# forcefoot.net
KiCad netlist of a schematic drawn in EAGLE
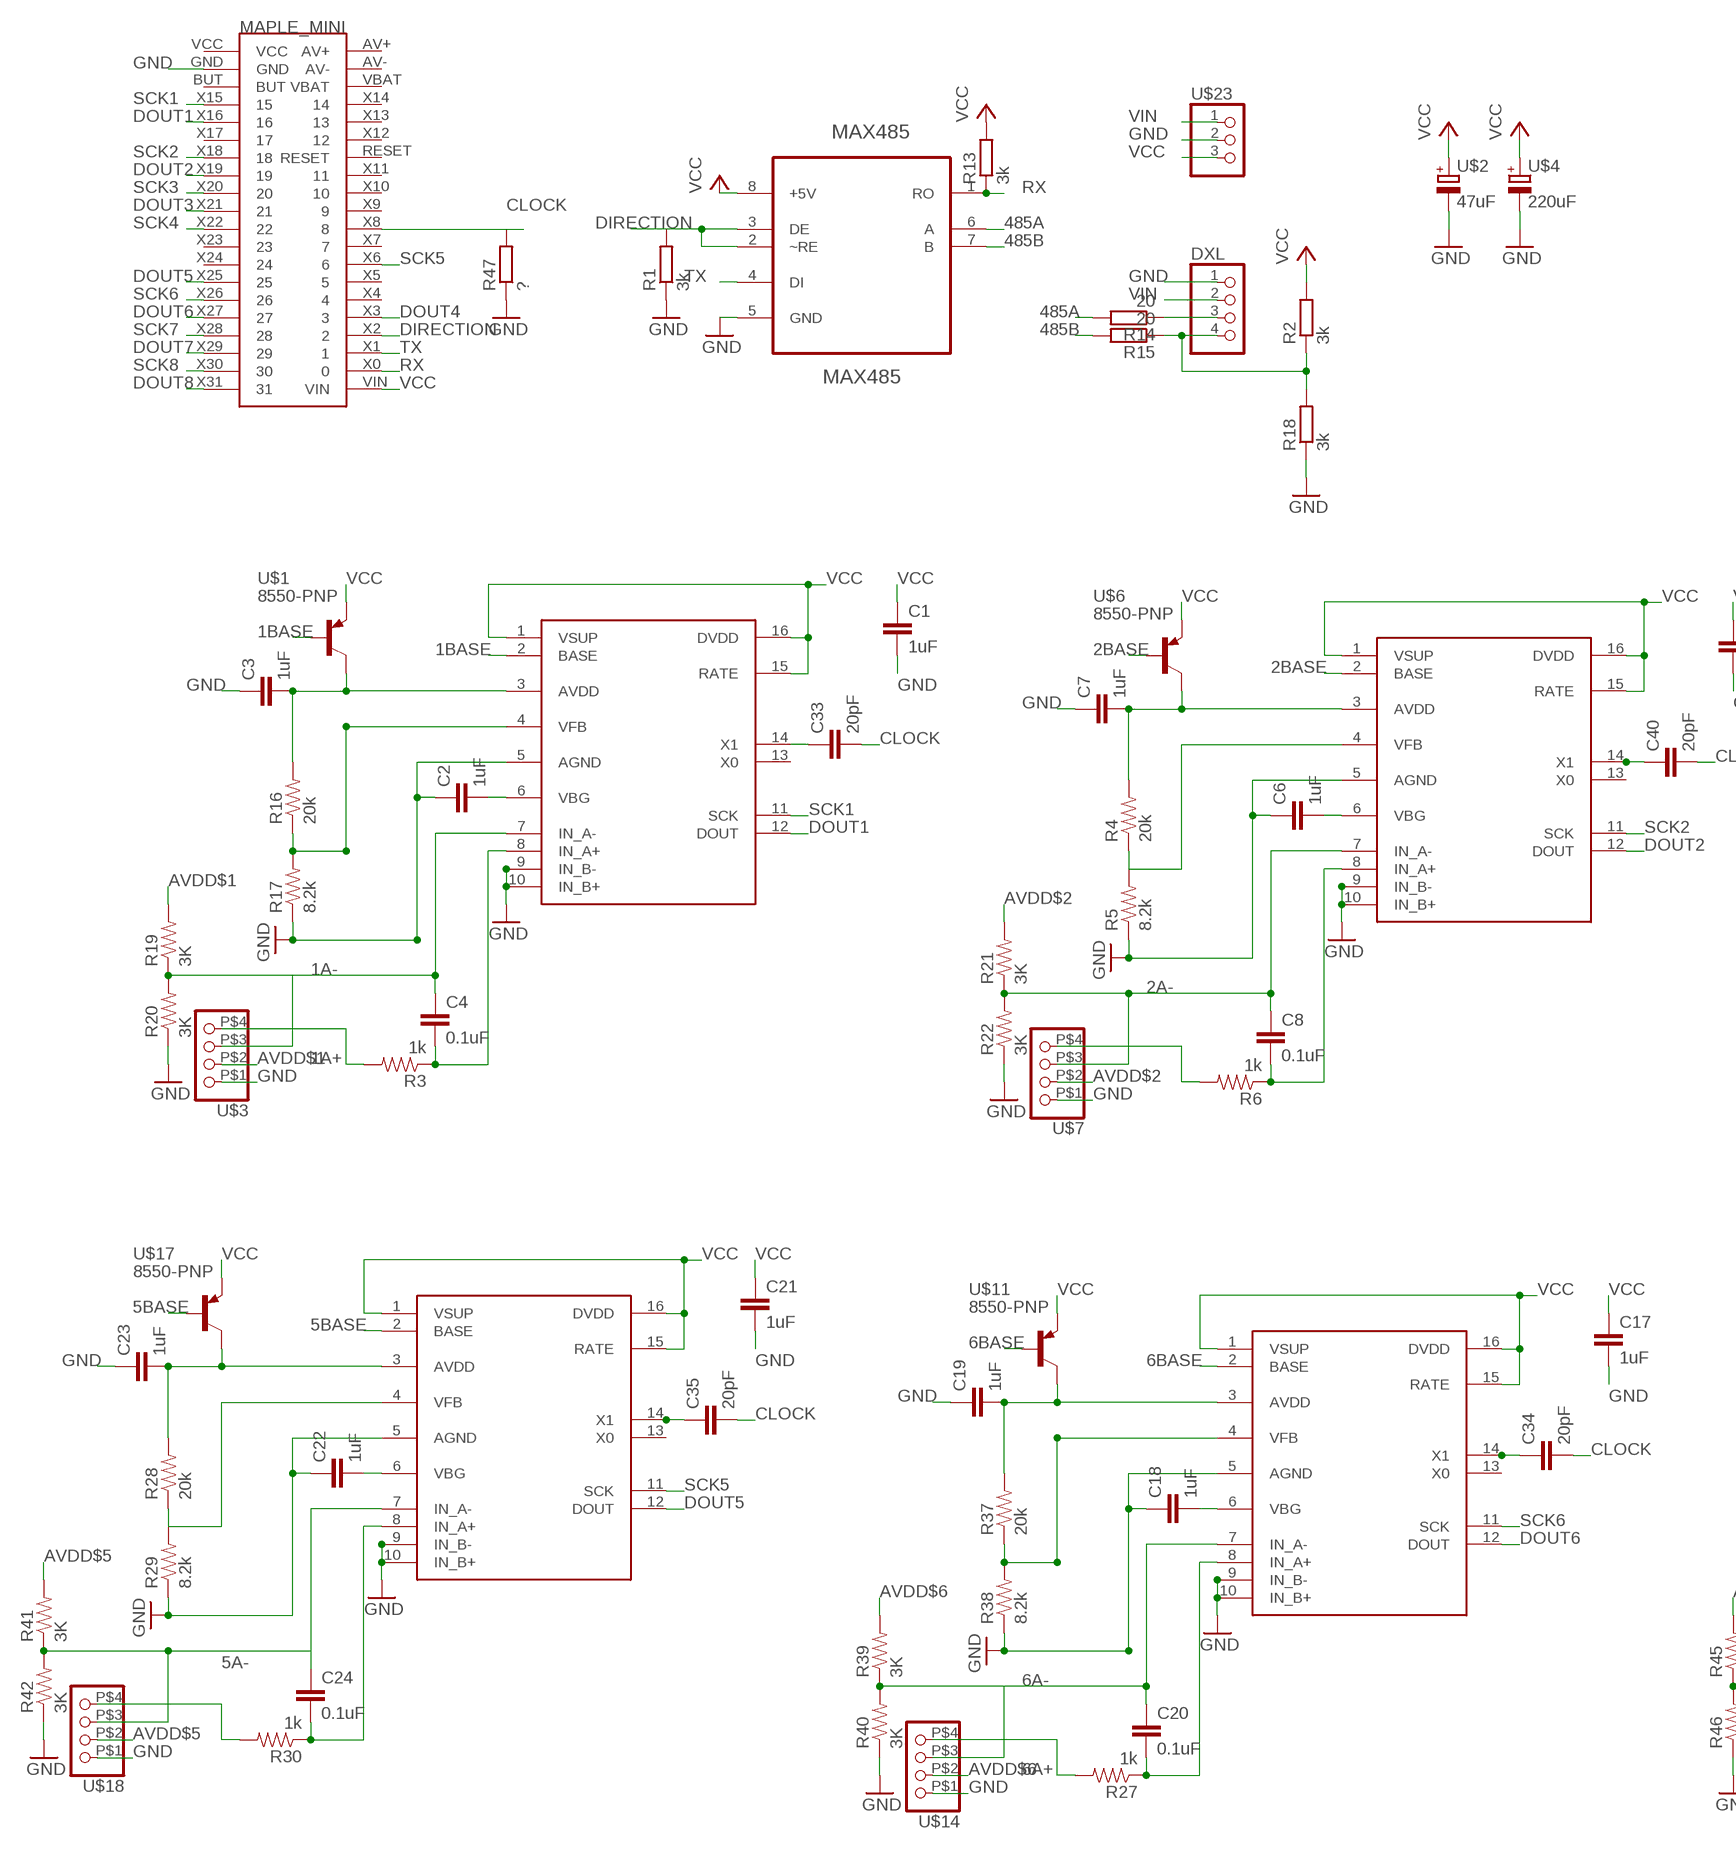
[diagram p0: schematic, sheet 1, part 1 of 2]
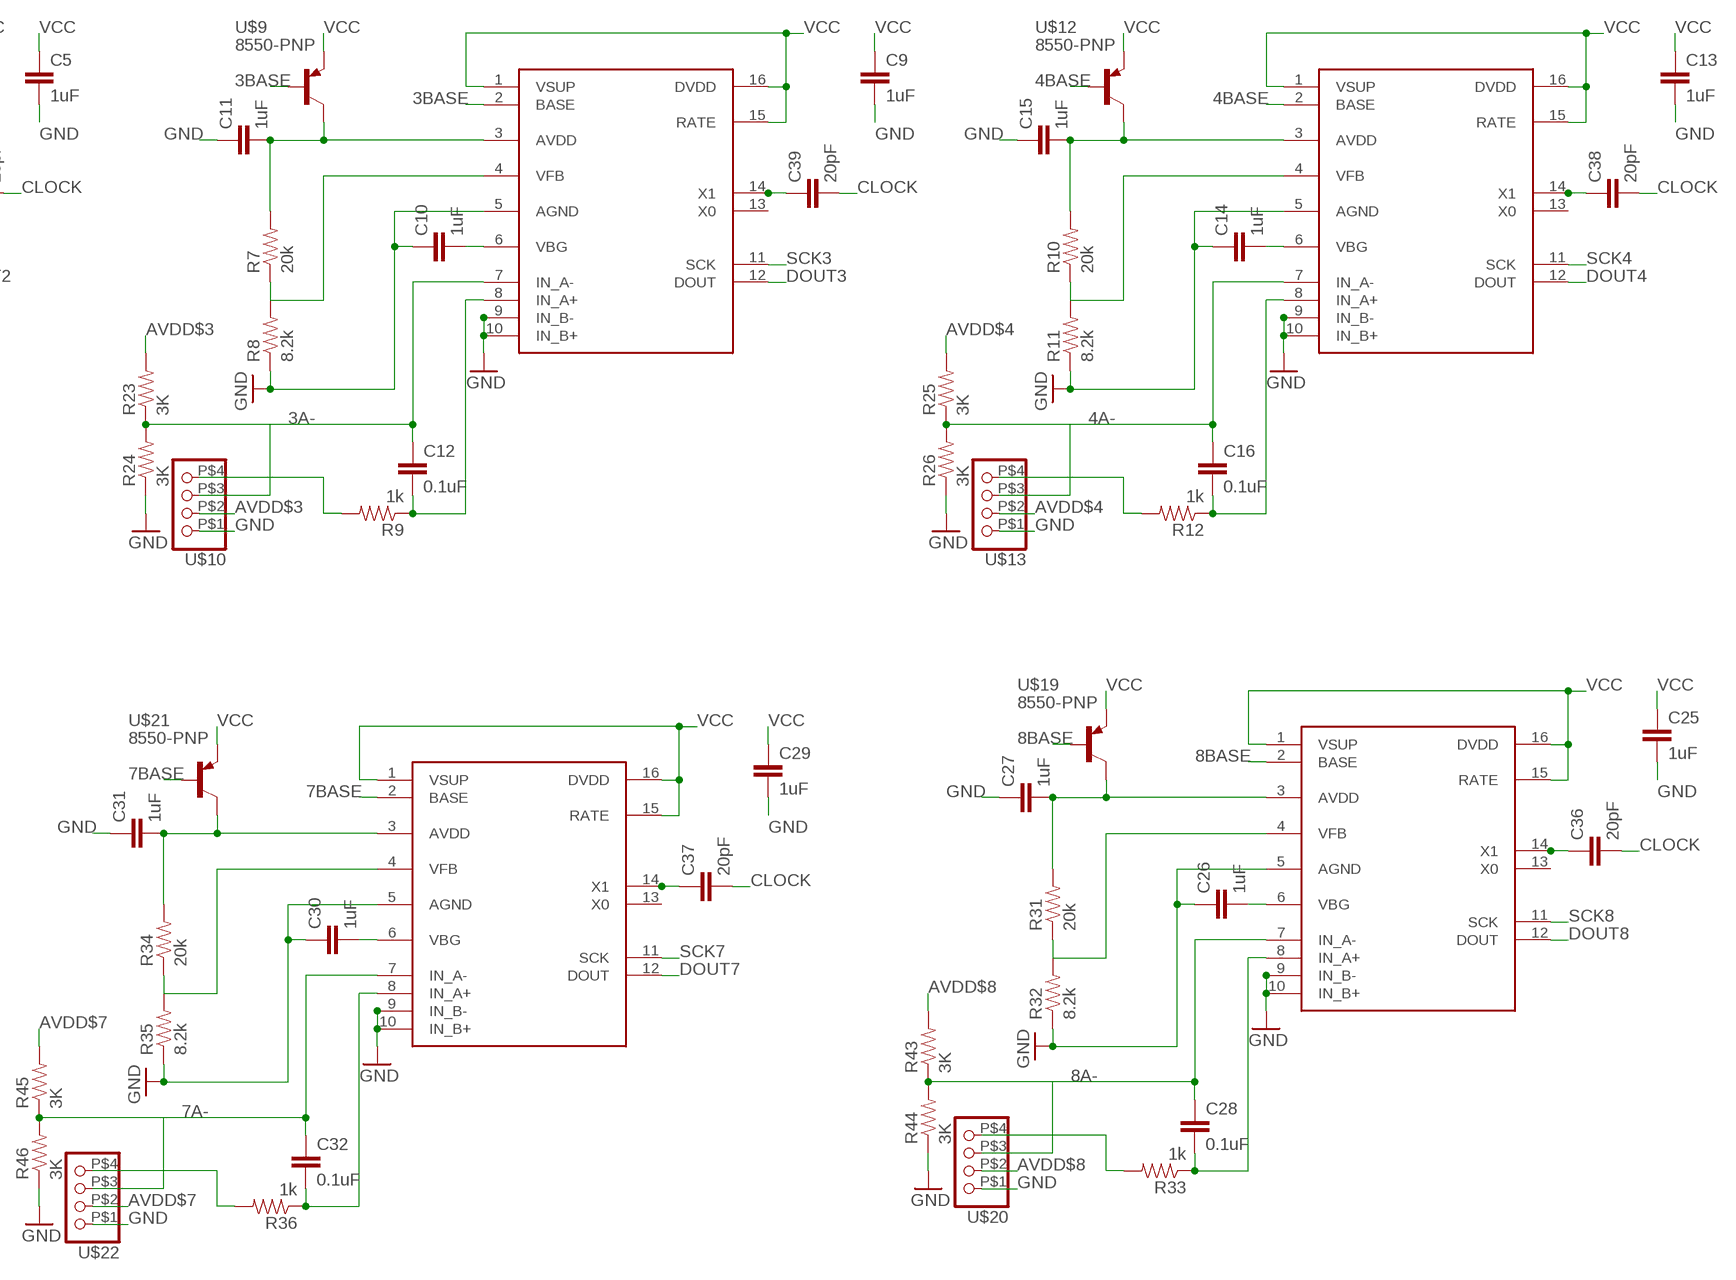
[diagram p1: schematic, sheet 1, part 2 of 2]

(export (version "E")
  (design (tool "Eeschema 10.0.6"))
  (components
    (comp (ref "C1")
      (value "1uF")
      (footprint "eagle-import:0805")
      (libsource (lib "eagle-import") (part "CAP0805"))
    )
    (comp (ref "C2")
      (value "1uF")
      (footprint "eagle-import:0805")
      (libsource (lib "eagle-import") (part "CAP0805"))
    )
    (comp (ref "C3")
      (value "1uF")
      (footprint "eagle-import:0805")
      (libsource (lib "eagle-import") (part "CAP0805"))
    )
    (comp (ref "C4")
      (value "0.1uF")
      (footprint "eagle-import:0805")
      (libsource (lib "eagle-import") (part "CAP0805"))
    )
    (comp (ref "C5")
      (value "1uF")
      (footprint "eagle-import:0805")
      (libsource (lib "eagle-import") (part "CAP0805"))
    )
    (comp (ref "C6")
      (value "1uF")
      (footprint "eagle-import:0805")
      (libsource (lib "eagle-import") (part "CAP0805"))
    )
    (comp (ref "C7")
      (value "1uF")
      (footprint "eagle-import:0805")
      (libsource (lib "eagle-import") (part "CAP0805"))
    )
    (comp (ref "C8")
      (value "0.1uF")
      (footprint "eagle-import:0805")
      (libsource (lib "eagle-import") (part "CAP0805"))
    )
    (comp (ref "C9")
      (value "1uF")
      (footprint "eagle-import:0805")
      (libsource (lib "eagle-import") (part "CAP0805"))
    )
    (comp (ref "C10")
      (value "1uF")
      (footprint "eagle-import:0805")
      (libsource (lib "eagle-import") (part "CAP0805"))
    )
    (comp (ref "C11")
      (value "1uF")
      (footprint "eagle-import:0805")
      (libsource (lib "eagle-import") (part "CAP0805"))
    )
    (comp (ref "C12")
      (value "0.1uF")
      (footprint "eagle-import:0805")
      (libsource (lib "eagle-import") (part "CAP0805"))
    )
    (comp (ref "C13")
      (value "1uF")
      (footprint "eagle-import:0805")
      (libsource (lib "eagle-import") (part "CAP0805"))
    )
    (comp (ref "C14")
      (value "1uF")
      (footprint "eagle-import:0805")
      (libsource (lib "eagle-import") (part "CAP0805"))
    )
    (comp (ref "C15")
      (value "1uF")
      (footprint "eagle-import:0805")
      (libsource (lib "eagle-import") (part "CAP0805"))
    )
    (comp (ref "C16")
      (value "0.1uF")
      (footprint "eagle-import:0805")
      (libsource (lib "eagle-import") (part "CAP0805"))
    )
    (comp (ref "C17")
      (value "1uF")
      (footprint "eagle-import:0805")
      (libsource (lib "eagle-import") (part "CAP0805"))
    )
    (comp (ref "C18")
      (value "1uF")
      (footprint "eagle-import:0805")
      (libsource (lib "eagle-import") (part "CAP0805"))
    )
    (comp (ref "C19")
      (value "1uF")
      (footprint "eagle-import:0805")
      (libsource (lib "eagle-import") (part "CAP0805"))
    )
    (comp (ref "C20")
      (value "0.1uF")
      (footprint "eagle-import:0805")
      (libsource (lib "eagle-import") (part "CAP0805"))
    )
    (comp (ref "C21")
      (value "1uF")
      (footprint "eagle-import:0805")
      (libsource (lib "eagle-import") (part "CAP0805"))
    )
    (comp (ref "C22")
      (value "1uF")
      (footprint "eagle-import:0805")
      (libsource (lib "eagle-import") (part "CAP0805"))
    )
    (comp (ref "C23")
      (value "1uF")
      (footprint "eagle-import:0805")
      (libsource (lib "eagle-import") (part "CAP0805"))
    )
    (comp (ref "C24")
      (value "0.1uF")
      (footprint "eagle-import:0805")
      (libsource (lib "eagle-import") (part "CAP0805"))
    )
    (comp (ref "C25")
      (value "1uF")
      (footprint "eagle-import:0805")
      (libsource (lib "eagle-import") (part "CAP0805"))
    )
    (comp (ref "C26")
      (value "1uF")
      (footprint "eagle-import:0805")
      (libsource (lib "eagle-import") (part "CAP0805"))
    )
    (comp (ref "C27")
      (value "1uF")
      (footprint "eagle-import:0805")
      (libsource (lib "eagle-import") (part "CAP0805"))
    )
    (comp (ref "C28")
      (value "0.1uF")
      (footprint "eagle-import:0805")
      (libsource (lib "eagle-import") (part "CAP0805"))
    )
    (comp (ref "C29")
      (value "1uF")
      (footprint "eagle-import:0805")
      (libsource (lib "eagle-import") (part "CAP0805"))
    )
    (comp (ref "C30")
      (value "1uF")
      (footprint "eagle-import:0805")
      (libsource (lib "eagle-import") (part "CAP0805"))
    )
    (comp (ref "C31")
      (value "1uF")
      (footprint "eagle-import:0805")
      (libsource (lib "eagle-import") (part "CAP0805"))
    )
    (comp (ref "C32")
      (value "0.1uF")
      (footprint "eagle-import:0805")
      (libsource (lib "eagle-import") (part "CAP0805"))
    )
    (comp (ref "C33")
      (value "20pF")
      (footprint "eagle-import:0805")
      (libsource (lib "eagle-import") (part "CAP0805"))
    )
    (comp (ref "C34")
      (value "20pF")
      (footprint "eagle-import:0805")
      (libsource (lib "eagle-import") (part "CAP0805"))
    )
    (comp (ref "C35")
      (value "20pF")
      (footprint "eagle-import:0805")
      (libsource (lib "eagle-import") (part "CAP0805"))
    )
    (comp (ref "C36")
      (value "20pF")
      (footprint "eagle-import:0805")
      (libsource (lib "eagle-import") (part "CAP0805"))
    )
    (comp (ref "C37")
      (value "20pF")
      (footprint "eagle-import:0805")
      (libsource (lib "eagle-import") (part "CAP0805"))
    )
    (comp (ref "C38")
      (value "20pF")
      (footprint "eagle-import:0805")
      (libsource (lib "eagle-import") (part "CAP0805"))
    )
    (comp (ref "C39")
      (value "20pF")
      (footprint "eagle-import:0805")
      (libsource (lib "eagle-import") (part "CAP0805"))
    )
    (comp (ref "C40")
      (value "20pF")
      (footprint "eagle-import:0805")
      (libsource (lib "eagle-import") (part "CAP0805"))
    )
    (comp (ref "DXL")
      (value "CONNEC_1X04\"")
      (footprint "eagle-import:CONNEC_1X04")
      (libsource (lib "eagle-import") (part "CONNEC_1X04{dblquote}"))
    )
    (comp (ref "HX1")
      (value "HX711SO16")
      (footprint "eagle-import:SO16")
      (libsource (lib "eagle-import") (part "HX711SO16"))
    )
    (comp (ref "HX2")
      (value "HX711SO16")
      (footprint "eagle-import:SO16")
      (libsource (lib "eagle-import") (part "HX711SO16"))
    )
    (comp (ref "HX3")
      (value "HX711SO16")
      (footprint "eagle-import:SO16")
      (libsource (lib "eagle-import") (part "HX711SO16"))
    )
    (comp (ref "HX4")
      (value "HX711SO16")
      (footprint "eagle-import:SO16")
      (libsource (lib "eagle-import") (part "HX711SO16"))
    )
    (comp (ref "HX5")
      (value "HX711SO16")
      (footprint "eagle-import:SO16")
      (libsource (lib "eagle-import") (part "HX711SO16"))
    )
    (comp (ref "HX6")
      (value "HX711SO16")
      (footprint "eagle-import:SO16")
      (libsource (lib "eagle-import") (part "HX711SO16"))
    )
    (comp (ref "HX7")
      (value "HX711SO16")
      (footprint "eagle-import:SO16")
      (libsource (lib "eagle-import") (part "HX711SO16"))
    )
    (comp (ref "HX8")
      (value "HX711SO16")
      (footprint "eagle-import:SO16")
      (libsource (lib "eagle-import") (part "HX711SO16"))
    )
    (comp (ref "MAPLE_MINI")
      (value "MAPLE_MINI")
      (footprint "eagle-import:CONNEC_2X20")
      (libsource (lib "eagle-import") (part "MAPLE_MINI"))
    )
    (comp (ref "MAX485")
      (value "MAX485")
      (footprint "eagle-import:SO8")
      (fields (field (name "MPN") "MAX485EESA+"))
      (libsource (lib "eagle-import") (part "MAX485"))
    )
    (comp (ref "R1")
      (value "3k")
      (footprint "eagle-import:R0805")
      (libsource (lib "eagle-import") (part "RESISTANCE-R0805"))
    )
    (comp (ref "R2")
      (value "3k")
      (footprint "eagle-import:R0805")
      (libsource (lib "eagle-import") (part "RESISTANCE-R0805"))
    )
    (comp (ref "R3")
      (value "1k")
      (footprint "eagle-import:0805")
      (libsource (lib "eagle-import") (part "RESISTOR0805-RES"))
    )
    (comp (ref "R4")
      (value "20k")
      (footprint "eagle-import:0805")
      (libsource (lib "eagle-import") (part "RESISTOR0805-RES"))
    )
    (comp (ref "R5")
      (value "8.2k")
      (footprint "eagle-import:0805")
      (libsource (lib "eagle-import") (part "RESISTOR0805-RES"))
    )
    (comp (ref "R6")
      (value "1k")
      (footprint "eagle-import:0805")
      (libsource (lib "eagle-import") (part "RESISTOR0805-RES"))
    )
    (comp (ref "R7")
      (value "20k")
      (footprint "eagle-import:0805")
      (libsource (lib "eagle-import") (part "RESISTOR0805-RES"))
    )
    (comp (ref "R8")
      (value "8.2k")
      (footprint "eagle-import:0805")
      (libsource (lib "eagle-import") (part "RESISTOR0805-RES"))
    )
    (comp (ref "R9")
      (value "1k")
      (footprint "eagle-import:0805")
      (libsource (lib "eagle-import") (part "RESISTOR0805-RES"))
    )
    (comp (ref "R10")
      (value "20k")
      (footprint "eagle-import:0805")
      (libsource (lib "eagle-import") (part "RESISTOR0805-RES"))
    )
    (comp (ref "R11")
      (value "8.2k")
      (footprint "eagle-import:0805")
      (libsource (lib "eagle-import") (part "RESISTOR0805-RES"))
    )
    (comp (ref "R12")
      (value "1k")
      (footprint "eagle-import:0805")
      (libsource (lib "eagle-import") (part "RESISTOR0805-RES"))
    )
    (comp (ref "R13")
      (value "3k")
      (footprint "eagle-import:R0805")
      (libsource (lib "eagle-import") (part "RESISTANCE-R0805"))
    )
    (comp (ref "R14")
      (value "20")
      (footprint "eagle-import:R0805")
      (libsource (lib "eagle-import") (part "RESISTANCE-R0805"))
    )
    (comp (ref "R15")
      (value "20")
      (footprint "eagle-import:R0805")
      (libsource (lib "eagle-import") (part "RESISTANCE-R0805"))
    )
    (comp (ref "R16")
      (value "20k")
      (footprint "eagle-import:0805")
      (libsource (lib "eagle-import") (part "RESISTOR0805-RES"))
    )
    (comp (ref "R17")
      (value "8.2k")
      (footprint "eagle-import:0805")
      (libsource (lib "eagle-import") (part "RESISTOR0805-RES"))
    )
    (comp (ref "R18")
      (value "3k")
      (footprint "eagle-import:R0805")
      (libsource (lib "eagle-import") (part "RESISTANCE-R0805"))
    )
    (comp (ref "R19")
      (value "3K")
      (footprint "eagle-import:0805")
      (libsource (lib "eagle-import") (part "RESISTOR0805-RES"))
    )
    (comp (ref "R20")
      (value "3K")
      (footprint "eagle-import:0805")
      (libsource (lib "eagle-import") (part "RESISTOR0805-RES"))
    )
    (comp (ref "R21")
      (value "3K")
      (footprint "eagle-import:0805")
      (libsource (lib "eagle-import") (part "RESISTOR0805-RES"))
    )
    (comp (ref "R22")
      (value "3K")
      (footprint "eagle-import:0805")
      (libsource (lib "eagle-import") (part "RESISTOR0805-RES"))
    )
    (comp (ref "R23")
      (value "3K")
      (footprint "eagle-import:0805")
      (libsource (lib "eagle-import") (part "RESISTOR0805-RES"))
    )
    (comp (ref "R24")
      (value "3K")
      (footprint "eagle-import:0805")
      (libsource (lib "eagle-import") (part "RESISTOR0805-RES"))
    )
    (comp (ref "R25")
      (value "3K")
      (footprint "eagle-import:0805")
      (libsource (lib "eagle-import") (part "RESISTOR0805-RES"))
    )
    (comp (ref "R26")
      (value "3K")
      (footprint "eagle-import:0805")
      (libsource (lib "eagle-import") (part "RESISTOR0805-RES"))
    )
    (comp (ref "R27")
      (value "1k")
      (footprint "eagle-import:0805")
      (libsource (lib "eagle-import") (part "RESISTOR0805-RES"))
    )
    (comp (ref "R28")
      (value "20k")
      (footprint "eagle-import:0805")
      (libsource (lib "eagle-import") (part "RESISTOR0805-RES"))
    )
    (comp (ref "R29")
      (value "8.2k")
      (footprint "eagle-import:0805")
      (libsource (lib "eagle-import") (part "RESISTOR0805-RES"))
    )
    (comp (ref "R30")
      (value "1k")
      (footprint "eagle-import:0805")
      (libsource (lib "eagle-import") (part "RESISTOR0805-RES"))
    )
    (comp (ref "R31")
      (value "20k")
      (footprint "eagle-import:0805")
      (libsource (lib "eagle-import") (part "RESISTOR0805-RES"))
    )
    (comp (ref "R32")
      (value "8.2k")
      (footprint "eagle-import:0805")
      (libsource (lib "eagle-import") (part "RESISTOR0805-RES"))
    )
    (comp (ref "R33")
      (value "1k")
      (footprint "eagle-import:0805")
      (libsource (lib "eagle-import") (part "RESISTOR0805-RES"))
    )
    (comp (ref "R34")
      (value "20k")
      (footprint "eagle-import:0805")
      (libsource (lib "eagle-import") (part "RESISTOR0805-RES"))
    )
    (comp (ref "R35")
      (value "8.2k")
      (footprint "eagle-import:0805")
      (libsource (lib "eagle-import") (part "RESISTOR0805-RES"))
    )
    (comp (ref "R36")
      (value "1k")
      (footprint "eagle-import:0805")
      (libsource (lib "eagle-import") (part "RESISTOR0805-RES"))
    )
    (comp (ref "R37")
      (value "20k")
      (footprint "eagle-import:0805")
      (libsource (lib "eagle-import") (part "RESISTOR0805-RES"))
    )
    (comp (ref "R38")
      (value "8.2k")
      (footprint "eagle-import:0805")
      (libsource (lib "eagle-import") (part "RESISTOR0805-RES"))
    )
    (comp (ref "R39")
      (value "3K")
      (footprint "eagle-import:0805")
      (libsource (lib "eagle-import") (part "RESISTOR0805-RES"))
    )
    (comp (ref "R40")
      (value "3K")
      (footprint "eagle-import:0805")
      (libsource (lib "eagle-import") (part "RESISTOR0805-RES"))
    )
    (comp (ref "R41")
      (value "3K")
      (footprint "eagle-import:0805")
      (libsource (lib "eagle-import") (part "RESISTOR0805-RES"))
    )
    (comp (ref "R42")
      (value "3K")
      (footprint "eagle-import:0805")
      (libsource (lib "eagle-import") (part "RESISTOR0805-RES"))
    )
    (comp (ref "R43")
      (value "3K")
      (footprint "eagle-import:0805")
      (libsource (lib "eagle-import") (part "RESISTOR0805-RES"))
    )
    (comp (ref "R44")
      (value "3K")
      (footprint "eagle-import:0805")
      (libsource (lib "eagle-import") (part "RESISTOR0805-RES"))
    )
    (comp (ref "R45")
      (value "3K")
      (footprint "eagle-import:0805")
      (libsource (lib "eagle-import") (part "RESISTOR0805-RES"))
    )
    (comp (ref "R46")
      (value "3K")
      (footprint "eagle-import:0805")
      (libsource (lib "eagle-import") (part "RESISTOR0805-RES"))
    )
    (comp (ref "R47")
      (value "?")
      (footprint "eagle-import:R0805")
      (libsource (lib "eagle-import") (part "RESISTANCE-R0805"))
    )
    (comp (ref "U$1")
      (value "8550-PNP")
      (footprint "eagle-import:SOT-23")
      (libsource (lib "eagle-import") (part "8550-PNP"))
    )
    (comp (ref "U$2")
      (value "47uF")
      (footprint "eagle-import:PANASONIC_D")
      (libsource (lib "eagle-import") (part "CPOL_EUPANASONIC_D"))
    )
    (comp (ref "U$3")
      (value "CONNEC_1X041.5")
      (footprint "eagle-import:4P1.5")
      (libsource (lib "eagle-import") (part "CONNEC_1X041.5"))
    )
    (comp (ref "U$4")
      (value "220uF")
      (footprint "eagle-import:PANASONIC_D8")
      (libsource (lib "eagle-import") (part "CPOL_EUPANASONIC_D8"))
    )
    (comp (ref "U$6")
      (value "8550-PNP")
      (footprint "eagle-import:SOT-23")
      (libsource (lib "eagle-import") (part "8550-PNP"))
    )
    (comp (ref "U$7")
      (value "CONNEC_1X041.5")
      (footprint "eagle-import:4P1.5")
      (libsource (lib "eagle-import") (part "CONNEC_1X041.5"))
    )
    (comp (ref "U$9")
      (value "8550-PNP")
      (footprint "eagle-import:SOT-23")
      (libsource (lib "eagle-import") (part "8550-PNP"))
    )
    (comp (ref "U$10")
      (value "CONNEC_1X041.5")
      (footprint "eagle-import:4P1.5")
      (libsource (lib "eagle-import") (part "CONNEC_1X041.5"))
    )
    (comp (ref "U$11")
      (value "8550-PNP")
      (footprint "eagle-import:SOT-23")
      (libsource (lib "eagle-import") (part "8550-PNP"))
    )
    (comp (ref "U$12")
      (value "8550-PNP")
      (footprint "eagle-import:SOT-23")
      (libsource (lib "eagle-import") (part "8550-PNP"))
    )
    (comp (ref "U$13")
      (value "CONNEC_1X041.5")
      (footprint "eagle-import:4P1.5")
      (libsource (lib "eagle-import") (part "CONNEC_1X041.5"))
    )
    (comp (ref "U$14")
      (value "CONNEC_1X041.5")
      (footprint "eagle-import:4P1.5")
      (libsource (lib "eagle-import") (part "CONNEC_1X041.5"))
    )
    (comp (ref "U$17")
      (value "8550-PNP")
      (footprint "eagle-import:SOT-23")
      (libsource (lib "eagle-import") (part "8550-PNP"))
    )
    (comp (ref "U$18")
      (value "CONNEC_1X041.5")
      (footprint "eagle-import:4P1.5")
      (libsource (lib "eagle-import") (part "CONNEC_1X041.5"))
    )
    (comp (ref "U$19")
      (value "8550-PNP")
      (footprint "eagle-import:SOT-23")
      (libsource (lib "eagle-import") (part "8550-PNP"))
    )
    (comp (ref "U$20")
      (value "CONNEC_1X041.5")
      (footprint "eagle-import:4P1.5")
      (libsource (lib "eagle-import") (part "CONNEC_1X041.5"))
    )
    (comp (ref "U$21")
      (value "8550-PNP")
      (footprint "eagle-import:SOT-23")
      (libsource (lib "eagle-import") (part "8550-PNP"))
    )
    (comp (ref "U$22")
      (value "CONNEC_1X041.5")
      (footprint "eagle-import:4P1.5")
      (libsource (lib "eagle-import") (part "CONNEC_1X041.5"))
    )
    (comp (ref "U$23")
      (value "CONNEC_1X03")
      (footprint "eagle-import:CONNEC_1X03")
      (libsource (lib "eagle-import") (part "CONNEC_1X03"))
    )
  )
  (nets
    (net (code "1") (name "/1A+") (class "Default")
      (node (ref "R3") (pin "2") (pinfunction "2_2") (pintype "passive"))
      (node (ref "U$3") (pin "P$4") (pinfunction "4_P$4") (pintype "passive"))
    )
    (net (code "2") (name "/1A-") (class "Default")
      (node (ref "C4") (pin "1") (pinfunction "1_1") (pintype "passive"))
      (node (ref "HX1") (pin "7") (pinfunction "IN_A-_7") (pintype "bidirectional"))
      (node (ref "R19") (pin "1") (pinfunction "1_1") (pintype "passive"))
      (node (ref "R20") (pin "2") (pinfunction "2_2") (pintype "passive"))
      (node (ref "U$3") (pin "P$3") (pinfunction "3_P$3") (pintype "passive"))
    )
    (net (code "3") (name "/1BASE") (class "Default")
      (node (ref "HX1") (pin "2") (pinfunction "BASE_2") (pintype "bidirectional"))
      (node (ref "U$1") (pin "1") (pinfunction "B_1") (pintype "passive"))
    )
    (net (code "4") (name "/2A-") (class "Default")
      (node (ref "C8") (pin "1") (pinfunction "1_1") (pintype "passive"))
      (node (ref "HX2") (pin "7") (pinfunction "IN_A-_7") (pintype "bidirectional"))
      (node (ref "R21") (pin "1") (pinfunction "1_1") (pintype "passive"))
      (node (ref "R22") (pin "2") (pinfunction "2_2") (pintype "passive"))
      (node (ref "U$7") (pin "P$3") (pinfunction "3_P$3") (pintype "passive"))
    )
    (net (code "5") (name "/2BASE") (class "Default")
      (node (ref "HX2") (pin "2") (pinfunction "BASE_2") (pintype "bidirectional"))
      (node (ref "U$6") (pin "1") (pinfunction "B_1") (pintype "passive"))
    )
    (net (code "6") (name "/3A-") (class "Default")
      (node (ref "C12") (pin "1") (pinfunction "1_1") (pintype "passive"))
      (node (ref "HX3") (pin "7") (pinfunction "IN_A-_7") (pintype "bidirectional"))
      (node (ref "R23") (pin "1") (pinfunction "1_1") (pintype "passive"))
      (node (ref "R24") (pin "2") (pinfunction "2_2") (pintype "passive"))
      (node (ref "U$10") (pin "P$3") (pinfunction "3_P$3") (pintype "passive"))
    )
    (net (code "7") (name "/3BASE") (class "Default")
      (node (ref "HX3") (pin "2") (pinfunction "BASE_2") (pintype "bidirectional"))
      (node (ref "U$9") (pin "1") (pinfunction "B_1") (pintype "passive"))
    )
    (net (code "8") (name "/4A-") (class "Default")
      (node (ref "C16") (pin "1") (pinfunction "1_1") (pintype "passive"))
      (node (ref "HX4") (pin "7") (pinfunction "IN_A-_7") (pintype "bidirectional"))
      (node (ref "R25") (pin "1") (pinfunction "1_1") (pintype "passive"))
      (node (ref "R26") (pin "2") (pinfunction "2_2") (pintype "passive"))
      (node (ref "U$13") (pin "P$3") (pinfunction "3_P$3") (pintype "passive"))
    )
    (net (code "9") (name "/4BASE") (class "Default")
      (node (ref "HX4") (pin "2") (pinfunction "BASE_2") (pintype "bidirectional"))
      (node (ref "U$12") (pin "1") (pinfunction "B_1") (pintype "passive"))
    )
    (net (code "10") (name "/5A-") (class "Default")
      (node (ref "C24") (pin "1") (pinfunction "1_1") (pintype "passive"))
      (node (ref "HX6") (pin "7") (pinfunction "IN_A-_7") (pintype "bidirectional"))
      (node (ref "R41") (pin "1") (pinfunction "1_1") (pintype "passive"))
      (node (ref "R42") (pin "2") (pinfunction "2_2") (pintype "passive"))
      (node (ref "U$18") (pin "P$3") (pinfunction "3_P$3") (pintype "passive"))
    )
    (net (code "11") (name "/5BASE") (class "Default")
      (node (ref "HX6") (pin "2") (pinfunction "BASE_2") (pintype "bidirectional"))
      (node (ref "U$17") (pin "1") (pinfunction "B_1") (pintype "passive"))
    )
    (net (code "12") (name "/6A+") (class "Default")
      (node (ref "R27") (pin "2") (pinfunction "2_2") (pintype "passive"))
      (node (ref "U$14") (pin "P$4") (pinfunction "4_P$4") (pintype "passive"))
    )
    (net (code "13") (name "/6A-") (class "Default")
      (node (ref "C20") (pin "1") (pinfunction "1_1") (pintype "passive"))
      (node (ref "HX5") (pin "7") (pinfunction "IN_A-_7") (pintype "bidirectional"))
      (node (ref "R39") (pin "1") (pinfunction "1_1") (pintype "passive"))
      (node (ref "R40") (pin "2") (pinfunction "2_2") (pintype "passive"))
      (node (ref "U$14") (pin "P$3") (pinfunction "3_P$3") (pintype "passive"))
    )
    (net (code "14") (name "/6BASE") (class "Default")
      (node (ref "HX5") (pin "2") (pinfunction "BASE_2") (pintype "bidirectional"))
      (node (ref "U$11") (pin "1") (pinfunction "B_1") (pintype "passive"))
    )
    (net (code "15") (name "/7A-") (class "Default")
      (node (ref "C32") (pin "1") (pinfunction "1_1") (pintype "passive"))
      (node (ref "HX8") (pin "7") (pinfunction "IN_A-_7") (pintype "bidirectional"))
      (node (ref "R45") (pin "1") (pinfunction "1_1") (pintype "passive"))
      (node (ref "R46") (pin "2") (pinfunction "2_2") (pintype "passive"))
      (node (ref "U$22") (pin "P$3") (pinfunction "3_P$3") (pintype "passive"))
    )
    (net (code "16") (name "/7BASE") (class "Default")
      (node (ref "HX8") (pin "2") (pinfunction "BASE_2") (pintype "bidirectional"))
      (node (ref "U$21") (pin "1") (pinfunction "B_1") (pintype "passive"))
    )
    (net (code "17") (name "/8A-") (class "Default")
      (node (ref "C28") (pin "1") (pinfunction "1_1") (pintype "passive"))
      (node (ref "HX7") (pin "7") (pinfunction "IN_A-_7") (pintype "bidirectional"))
      (node (ref "R43") (pin "1") (pinfunction "1_1") (pintype "passive"))
      (node (ref "R44") (pin "2") (pinfunction "2_2") (pintype "passive"))
      (node (ref "U$20") (pin "P$3") (pinfunction "3_P$3") (pintype "passive"))
    )
    (net (code "18") (name "/8BASE") (class "Default")
      (node (ref "HX7") (pin "2") (pinfunction "BASE_2") (pintype "bidirectional"))
      (node (ref "U$19") (pin "1") (pinfunction "B_1") (pintype "passive"))
    )
    (net (code "19") (name "/485A") (class "Default")
      (node (ref "MAX485") (pin "6") (pinfunction "A_6") (pintype "bidirectional"))
      (node (ref "R14") (pin "2") (pinfunction "2_2") (pintype "passive"))
    )
    (net (code "20") (name "/485B") (class "Default")
      (node (ref "MAX485") (pin "7") (pinfunction "B_7") (pintype "bidirectional"))
      (node (ref "R15") (pin "2") (pinfunction "2_2") (pintype "passive"))
    )
    (net (code "21") (name "/AVDD$1") (class "Default")
      (node (ref "C3") (pin "2") (pinfunction "2_2") (pintype "passive"))
      (node (ref "HX1") (pin "3") (pinfunction "AVDD_3") (pintype "bidirectional"))
      (node (ref "R16") (pin "2") (pinfunction "2_2") (pintype "passive"))
      (node (ref "R19") (pin "2") (pinfunction "2_2") (pintype "passive"))
      (node (ref "U$1") (pin "3") (pinfunction "C_3") (pintype "passive"))
      (node (ref "U$3") (pin "P$2") (pinfunction "2_P$2") (pintype "passive"))
    )
    (net (code "22") (name "/AVDD$2") (class "Default")
      (node (ref "C7") (pin "2") (pinfunction "2_2") (pintype "passive"))
      (node (ref "HX2") (pin "3") (pinfunction "AVDD_3") (pintype "bidirectional"))
      (node (ref "R21") (pin "2") (pinfunction "2_2") (pintype "passive"))
      (node (ref "R4") (pin "2") (pinfunction "2_2") (pintype "passive"))
      (node (ref "U$6") (pin "3") (pinfunction "C_3") (pintype "passive"))
      (node (ref "U$7") (pin "P$2") (pinfunction "2_P$2") (pintype "passive"))
    )
    (net (code "23") (name "/AVDD$3") (class "Default")
      (node (ref "C11") (pin "2") (pinfunction "2_2") (pintype "passive"))
      (node (ref "HX3") (pin "3") (pinfunction "AVDD_3") (pintype "bidirectional"))
      (node (ref "R23") (pin "2") (pinfunction "2_2") (pintype "passive"))
      (node (ref "R7") (pin "2") (pinfunction "2_2") (pintype "passive"))
      (node (ref "U$10") (pin "P$2") (pinfunction "2_P$2") (pintype "passive"))
      (node (ref "U$9") (pin "3") (pinfunction "C_3") (pintype "passive"))
    )
    (net (code "24") (name "/AVDD$4") (class "Default")
      (node (ref "C15") (pin "2") (pinfunction "2_2") (pintype "passive"))
      (node (ref "HX4") (pin "3") (pinfunction "AVDD_3") (pintype "bidirectional"))
      (node (ref "R10") (pin "2") (pinfunction "2_2") (pintype "passive"))
      (node (ref "R25") (pin "2") (pinfunction "2_2") (pintype "passive"))
      (node (ref "U$12") (pin "3") (pinfunction "C_3") (pintype "passive"))
      (node (ref "U$13") (pin "P$2") (pinfunction "2_P$2") (pintype "passive"))
    )
    (net (code "25") (name "/AVDD$5") (class "Default")
      (node (ref "C23") (pin "2") (pinfunction "2_2") (pintype "passive"))
      (node (ref "HX6") (pin "3") (pinfunction "AVDD_3") (pintype "bidirectional"))
      (node (ref "R28") (pin "2") (pinfunction "2_2") (pintype "passive"))
      (node (ref "R41") (pin "2") (pinfunction "2_2") (pintype "passive"))
      (node (ref "U$17") (pin "3") (pinfunction "C_3") (pintype "passive"))
      (node (ref "U$18") (pin "P$2") (pinfunction "2_P$2") (pintype "passive"))
    )
    (net (code "26") (name "/AVDD$6") (class "Default")
      (node (ref "C19") (pin "2") (pinfunction "2_2") (pintype "passive"))
      (node (ref "HX5") (pin "3") (pinfunction "AVDD_3") (pintype "bidirectional"))
      (node (ref "R37") (pin "2") (pinfunction "2_2") (pintype "passive"))
      (node (ref "R39") (pin "2") (pinfunction "2_2") (pintype "passive"))
      (node (ref "U$11") (pin "3") (pinfunction "C_3") (pintype "passive"))
      (node (ref "U$14") (pin "P$2") (pinfunction "2_P$2") (pintype "passive"))
    )
    (net (code "27") (name "/AVDD$7") (class "Default")
      (node (ref "C31") (pin "2") (pinfunction "2_2") (pintype "passive"))
      (node (ref "HX8") (pin "3") (pinfunction "AVDD_3") (pintype "bidirectional"))
      (node (ref "R34") (pin "2") (pinfunction "2_2") (pintype "passive"))
      (node (ref "R45") (pin "2") (pinfunction "2_2") (pintype "passive"))
      (node (ref "U$21") (pin "3") (pinfunction "C_3") (pintype "passive"))
      (node (ref "U$22") (pin "P$2") (pinfunction "2_P$2") (pintype "passive"))
    )
    (net (code "28") (name "/AVDD$8") (class "Default")
      (node (ref "C27") (pin "2") (pinfunction "2_2") (pintype "passive"))
      (node (ref "HX7") (pin "3") (pinfunction "AVDD_3") (pintype "bidirectional"))
      (node (ref "R31") (pin "2") (pinfunction "2_2") (pintype "passive"))
      (node (ref "R43") (pin "2") (pinfunction "2_2") (pintype "passive"))
      (node (ref "U$19") (pin "3") (pinfunction "C_3") (pintype "passive"))
      (node (ref "U$20") (pin "P$2") (pinfunction "2_P$2") (pintype "passive"))
    )
    (net (code "29") (name "/CLOCK") (class "Default")
      (node (ref "C33") (pin "2") (pinfunction "2_2") (pintype "passive"))
      (node (ref "C34") (pin "2") (pinfunction "2_2") (pintype "passive"))
      (node (ref "C35") (pin "2") (pinfunction "2_2") (pintype "passive"))
      (node (ref "C36") (pin "2") (pinfunction "2_2") (pintype "passive"))
      (node (ref "C37") (pin "2") (pinfunction "2_2") (pintype "passive"))
      (node (ref "C38") (pin "2") (pinfunction "2_2") (pintype "passive"))
      (node (ref "C39") (pin "2") (pinfunction "2_2") (pintype "passive"))
      (node (ref "C40") (pin "2") (pinfunction "2_2") (pintype "passive"))
      (node (ref "MAPLE_MINI") (pin "X8") (pinfunction "8_X8") (pintype "bidirectional"))
      (node (ref "R47") (pin "2") (pinfunction "2_2") (pintype "passive"))
    )
    (net (code "30") (name "/DIRECTION") (class "Default")
      (node (ref "MAPLE_MINI") (pin "X2") (pinfunction "2_X2") (pintype "bidirectional"))
      (node (ref "MAX485") (pin "2") (pinfunction "~{RE}_2") (pintype "input"))
      (node (ref "MAX485") (pin "3") (pinfunction "DE_3") (pintype "input"))
      (node (ref "R1") (pin "2") (pinfunction "2_2") (pintype "passive"))
    )
    (net (code "31") (name "/DOUT1") (class "Default")
      (node (ref "HX1") (pin "12") (pinfunction "DOUT_12") (pintype "bidirectional"))
      (node (ref "MAPLE_MINI") (pin "X16") (pinfunction "16_X16") (pintype "bidirectional"))
    )
    (net (code "32") (name "/DOUT2") (class "Default")
      (node (ref "HX2") (pin "12") (pinfunction "DOUT_12") (pintype "bidirectional"))
      (node (ref "MAPLE_MINI") (pin "X19") (pinfunction "19_X19") (pintype "bidirectional"))
    )
    (net (code "33") (name "/DOUT3") (class "Default")
      (node (ref "HX3") (pin "12") (pinfunction "DOUT_12") (pintype "bidirectional"))
      (node (ref "MAPLE_MINI") (pin "X21") (pinfunction "21_X21") (pintype "bidirectional"))
    )
    (net (code "34") (name "/DOUT4") (class "Default")
      (node (ref "HX4") (pin "12") (pinfunction "DOUT_12") (pintype "bidirectional"))
      (node (ref "MAPLE_MINI") (pin "X3") (pinfunction "3_X3") (pintype "bidirectional"))
    )
    (net (code "35") (name "/DOUT5") (class "Default")
      (node (ref "HX6") (pin "12") (pinfunction "DOUT_12") (pintype "bidirectional"))
      (node (ref "MAPLE_MINI") (pin "X25") (pinfunction "25_X25") (pintype "bidirectional"))
    )
    (net (code "36") (name "/DOUT6") (class "Default")
      (node (ref "HX5") (pin "12") (pinfunction "DOUT_12") (pintype "bidirectional"))
      (node (ref "MAPLE_MINI") (pin "X27") (pinfunction "27_X27") (pintype "bidirectional"))
    )
    (net (code "37") (name "/DOUT7") (class "Default")
      (node (ref "HX8") (pin "12") (pinfunction "DOUT_12") (pintype "bidirectional"))
      (node (ref "MAPLE_MINI") (pin "X29") (pinfunction "29_X29") (pintype "bidirectional"))
    )
    (net (code "38") (name "/DOUT8") (class "Default")
      (node (ref "HX7") (pin "12") (pinfunction "DOUT_12") (pintype "bidirectional"))
      (node (ref "MAPLE_MINI") (pin "X31") (pinfunction "31_X31") (pintype "bidirectional"))
    )
    (net (code "39") (name "/RX") (class "Default")
      (node (ref "MAPLE_MINI") (pin "X0") (pinfunction "0_X0") (pintype "bidirectional"))
      (node (ref "MAX485") (pin "1") (pinfunction "RO_1") (pintype "output"))
      (node (ref "R13") (pin "1") (pinfunction "1_1") (pintype "passive"))
    )
    (net (code "40") (name "/SCK1") (class "Default")
      (node (ref "HX1") (pin "11") (pinfunction "SCK_11") (pintype "bidirectional"))
      (node (ref "MAPLE_MINI") (pin "X15") (pinfunction "15_X15") (pintype "bidirectional"))
    )
    (net (code "41") (name "/SCK2") (class "Default")
      (node (ref "HX2") (pin "11") (pinfunction "SCK_11") (pintype "bidirectional"))
      (node (ref "MAPLE_MINI") (pin "X18") (pinfunction "18_X18") (pintype "bidirectional"))
    )
    (net (code "42") (name "/SCK3") (class "Default")
      (node (ref "HX3") (pin "11") (pinfunction "SCK_11") (pintype "bidirectional"))
      (node (ref "MAPLE_MINI") (pin "X20") (pinfunction "20_X20") (pintype "bidirectional"))
    )
    (net (code "43") (name "/SCK4") (class "Default")
      (node (ref "HX4") (pin "11") (pinfunction "SCK_11") (pintype "bidirectional"))
      (node (ref "MAPLE_MINI") (pin "X22") (pinfunction "22_X22") (pintype "bidirectional"))
    )
    (net (code "44") (name "/SCK5") (class "Default")
      (node (ref "HX6") (pin "11") (pinfunction "SCK_11") (pintype "bidirectional"))
      (node (ref "MAPLE_MINI") (pin "X6") (pinfunction "6_X6") (pintype "bidirectional"))
    )
    (net (code "45") (name "/SCK6") (class "Default")
      (node (ref "HX5") (pin "11") (pinfunction "SCK_11") (pintype "bidirectional"))
      (node (ref "MAPLE_MINI") (pin "X26") (pinfunction "26_X26") (pintype "bidirectional"))
    )
    (net (code "46") (name "/SCK7") (class "Default")
      (node (ref "HX8") (pin "11") (pinfunction "SCK_11") (pintype "bidirectional"))
      (node (ref "MAPLE_MINI") (pin "X28") (pinfunction "28_X28") (pintype "bidirectional"))
    )
    (net (code "47") (name "/SCK8") (class "Default")
      (node (ref "HX7") (pin "11") (pinfunction "SCK_11") (pintype "bidirectional"))
      (node (ref "MAPLE_MINI") (pin "X30") (pinfunction "30_X30") (pintype "bidirectional"))
    )
    (net (code "48") (name "/TX") (class "Default")
      (node (ref "MAPLE_MINI") (pin "X1") (pinfunction "1_X1") (pintype "bidirectional"))
      (node (ref "MAX485") (pin "4") (pinfunction "DI_4") (pintype "input"))
    )
    (net (code "49") (name "/VIN") (class "Default")
      (node (ref "DXL") (pin "2") (pinfunction "2_2") (pintype "passive"))
      (node (ref "U$23") (pin "1") (pinfunction "1_1") (pintype "passive"))
    )
    (net (code "50") (name "GND") (class "Default")
      (node (ref "C1") (pin "2") (pinfunction "2_2") (pintype "passive"))
      (node (ref "C10") (pin "1") (pinfunction "1_1") (pintype "passive"))
      (node (ref "C11") (pin "1") (pinfunction "1_1") (pintype "passive"))
      (node (ref "C13") (pin "2") (pinfunction "2_2") (pintype "passive"))
      (node (ref "C14") (pin "1") (pinfunction "1_1") (pintype "passive"))
      (node (ref "C15") (pin "1") (pinfunction "1_1") (pintype "passive"))
      (node (ref "C17") (pin "2") (pinfunction "2_2") (pintype "passive"))
      (node (ref "C18") (pin "1") (pinfunction "1_1") (pintype "passive"))
      (node (ref "C19") (pin "1") (pinfunction "1_1") (pintype "passive"))
      (node (ref "C2") (pin "1") (pinfunction "1_1") (pintype "passive"))
      (node (ref "C21") (pin "2") (pinfunction "2_2") (pintype "passive"))
      (node (ref "C22") (pin "1") (pinfunction "1_1") (pintype "passive"))
      (node (ref "C23") (pin "1") (pinfunction "1_1") (pintype "passive"))
      (node (ref "C25") (pin "2") (pinfunction "2_2") (pintype "passive"))
      (node (ref "C26") (pin "1") (pinfunction "1_1") (pintype "passive"))
      (node (ref "C27") (pin "1") (pinfunction "1_1") (pintype "passive"))
      (node (ref "C29") (pin "2") (pinfunction "2_2") (pintype "passive"))
      (node (ref "C3") (pin "1") (pinfunction "1_1") (pintype "passive"))
      (node (ref "C30") (pin "1") (pinfunction "1_1") (pintype "passive"))
      (node (ref "C31") (pin "1") (pinfunction "1_1") (pintype "passive"))
      (node (ref "C5") (pin "2") (pinfunction "2_2") (pintype "passive"))
      (node (ref "C6") (pin "1") (pinfunction "1_1") (pintype "passive"))
      (node (ref "C7") (pin "1") (pinfunction "1_1") (pintype "passive"))
      (node (ref "C9") (pin "2") (pinfunction "2_2") (pintype "passive"))
      (node (ref "DXL") (pin "1") (pinfunction "1_1") (pintype "passive"))
      (node (ref "HX1") (pin "10") (pinfunction "IN_B+_10") (pintype "bidirectional"))
      (node (ref "HX1") (pin "5") (pinfunction "AGND_5") (pintype "bidirectional"))
      (node (ref "HX1") (pin "9") (pinfunction "IN_B-_9") (pintype "bidirectional"))
      (node (ref "HX2") (pin "10") (pinfunction "IN_B+_10") (pintype "bidirectional"))
      (node (ref "HX2") (pin "5") (pinfunction "AGND_5") (pintype "bidirectional"))
      (node (ref "HX2") (pin "9") (pinfunction "IN_B-_9") (pintype "bidirectional"))
      (node (ref "HX3") (pin "10") (pinfunction "IN_B+_10") (pintype "bidirectional"))
      (node (ref "HX3") (pin "5") (pinfunction "AGND_5") (pintype "bidirectional"))
      (node (ref "HX3") (pin "9") (pinfunction "IN_B-_9") (pintype "bidirectional"))
      (node (ref "HX4") (pin "10") (pinfunction "IN_B+_10") (pintype "bidirectional"))
      (node (ref "HX4") (pin "5") (pinfunction "AGND_5") (pintype "bidirectional"))
      (node (ref "HX4") (pin "9") (pinfunction "IN_B-_9") (pintype "bidirectional"))
      (node (ref "HX5") (pin "10") (pinfunction "IN_B+_10") (pintype "bidirectional"))
      (node (ref "HX5") (pin "5") (pinfunction "AGND_5") (pintype "bidirectional"))
      (node (ref "HX5") (pin "9") (pinfunction "IN_B-_9") (pintype "bidirectional"))
      (node (ref "HX6") (pin "10") (pinfunction "IN_B+_10") (pintype "bidirectional"))
      (node (ref "HX6") (pin "5") (pinfunction "AGND_5") (pintype "bidirectional"))
      (node (ref "HX6") (pin "9") (pinfunction "IN_B-_9") (pintype "bidirectional"))
      (node (ref "HX7") (pin "10") (pinfunction "IN_B+_10") (pintype "bidirectional"))
      (node (ref "HX7") (pin "5") (pinfunction "AGND_5") (pintype "bidirectional"))
      (node (ref "HX7") (pin "9") (pinfunction "IN_B-_9") (pintype "bidirectional"))
      (node (ref "HX8") (pin "10") (pinfunction "IN_B+_10") (pintype "bidirectional"))
      (node (ref "HX8") (pin "5") (pinfunction "AGND_5") (pintype "bidirectional"))
      (node (ref "HX8") (pin "9") (pinfunction "IN_B-_9") (pintype "bidirectional"))
      (node (ref "MAPLE_MINI") (pin "GND") (pinfunction "GND_GND") (pintype "bidirectional"))
      (node (ref "MAX485") (pin "5") (pinfunction "GND_5") (pintype "passive"))
      (node (ref "R1") (pin "1") (pinfunction "1_1") (pintype "passive"))
      (node (ref "R11") (pin "1") (pinfunction "1_1") (pintype "passive"))
      (node (ref "R17") (pin "1") (pinfunction "1_1") (pintype "passive"))
      (node (ref "R18") (pin "1") (pinfunction "1_1") (pintype "passive"))
      (node (ref "R20") (pin "1") (pinfunction "1_1") (pintype "passive"))
      (node (ref "R22") (pin "1") (pinfunction "1_1") (pintype "passive"))
      (node (ref "R24") (pin "1") (pinfunction "1_1") (pintype "passive"))
      (node (ref "R26") (pin "1") (pinfunction "1_1") (pintype "passive"))
      (node (ref "R29") (pin "1") (pinfunction "1_1") (pintype "passive"))
      (node (ref "R32") (pin "1") (pinfunction "1_1") (pintype "passive"))
      (node (ref "R35") (pin "1") (pinfunction "1_1") (pintype "passive"))
      (node (ref "R38") (pin "1") (pinfunction "1_1") (pintype "passive"))
      (node (ref "R40") (pin "1") (pinfunction "1_1") (pintype "passive"))
      (node (ref "R42") (pin "1") (pinfunction "1_1") (pintype "passive"))
      (node (ref "R44") (pin "1") (pinfunction "1_1") (pintype "passive"))
      (node (ref "R46") (pin "1") (pinfunction "1_1") (pintype "passive"))
      (node (ref "R47") (pin "1") (pinfunction "1_1") (pintype "passive"))
      (node (ref "R5") (pin "1") (pinfunction "1_1") (pintype "passive"))
      (node (ref "R8") (pin "1") (pinfunction "1_1") (pintype "passive"))
      (node (ref "U$10") (pin "P$1") (pinfunction "1_P$1") (pintype "passive"))
      (node (ref "U$13") (pin "P$1") (pinfunction "1_P$1") (pintype "passive"))
      (node (ref "U$14") (pin "P$1") (pinfunction "1_P$1") (pintype "passive"))
      (node (ref "U$18") (pin "P$1") (pinfunction "1_P$1") (pintype "passive"))
      (node (ref "U$2") (pin "-") (pinfunction "-_-") (pintype "passive"))
      (node (ref "U$20") (pin "P$1") (pinfunction "1_P$1") (pintype "passive"))
      (node (ref "U$22") (pin "P$1") (pinfunction "1_P$1") (pintype "passive"))
      (node (ref "U$23") (pin "2") (pinfunction "2_2") (pintype "passive"))
      (node (ref "U$3") (pin "P$1") (pinfunction "1_P$1") (pintype "passive"))
      (node (ref "U$4") (pin "-") (pinfunction "-_-") (pintype "passive"))
      (node (ref "U$7") (pin "P$1") (pinfunction "1_P$1") (pintype "passive"))
    )
    (net (code "51") (name "Net-(DXL-Pad3)") (class "Default")
      (node (ref "DXL") (pin "3") (pinfunction "3_3") (pintype "passive"))
      (node (ref "R14") (pin "1") (pinfunction "1_1") (pintype "passive"))
    )
    (net (code "52") (name "Net-(DXL-Pad4)") (class "Default")
      (node (ref "DXL") (pin "4") (pinfunction "4_4") (pintype "passive"))
      (node (ref "R15") (pin "1") (pinfunction "1_1") (pintype "passive"))
      (node (ref "R18") (pin "2") (pinfunction "2_2") (pintype "passive"))
      (node (ref "R2") (pin "1") (pinfunction "1_1") (pintype "passive"))
    )
    (net (code "53") (name "Net-(HX1-IN_A+)") (class "Default")
      (node (ref "C4") (pin "2") (pinfunction "2_2") (pintype "passive"))
      (node (ref "HX1") (pin "8") (pinfunction "IN_A+_8") (pintype "bidirectional"))
      (node (ref "R3") (pin "1") (pinfunction "1_1") (pintype "passive"))
    )
    (net (code "54") (name "Net-(HX1-VBG)") (class "Default")
      (node (ref "C2") (pin "2") (pinfunction "2_2") (pintype "passive"))
      (node (ref "HX1") (pin "6") (pinfunction "VBG_6") (pintype "bidirectional"))
    )
    (net (code "55") (name "Net-(HX1-VFB)") (class "Default")
      (node (ref "HX1") (pin "4") (pinfunction "VFB_4") (pintype "bidirectional"))
      (node (ref "R16") (pin "1") (pinfunction "1_1") (pintype "passive"))
      (node (ref "R17") (pin "2") (pinfunction "2_2") (pintype "passive"))
    )
    (net (code "56") (name "Net-(HX1-X1)") (class "Default")
      (node (ref "C33") (pin "1") (pinfunction "1_1") (pintype "passive"))
      (node (ref "HX1") (pin "14") (pinfunction "X1_14") (pintype "bidirectional"))
    )
    (net (code "57") (name "Net-(HX2-IN_A+)") (class "Default")
      (node (ref "C8") (pin "2") (pinfunction "2_2") (pintype "passive"))
      (node (ref "HX2") (pin "8") (pinfunction "IN_A+_8") (pintype "bidirectional"))
      (node (ref "R6") (pin "1") (pinfunction "1_1") (pintype "passive"))
    )
    (net (code "58") (name "Net-(HX2-VBG)") (class "Default")
      (node (ref "C6") (pin "2") (pinfunction "2_2") (pintype "passive"))
      (node (ref "HX2") (pin "6") (pinfunction "VBG_6") (pintype "bidirectional"))
    )
    (net (code "59") (name "Net-(HX2-VFB)") (class "Default")
      (node (ref "HX2") (pin "4") (pinfunction "VFB_4") (pintype "bidirectional"))
      (node (ref "R4") (pin "1") (pinfunction "1_1") (pintype "passive"))
      (node (ref "R5") (pin "2") (pinfunction "2_2") (pintype "passive"))
    )
    (net (code "60") (name "Net-(HX2-X1)") (class "Default")
      (node (ref "C40") (pin "1") (pinfunction "1_1") (pintype "passive"))
      (node (ref "HX2") (pin "14") (pinfunction "X1_14") (pintype "bidirectional"))
    )
    (net (code "61") (name "Net-(HX3-IN_A+)") (class "Default")
      (node (ref "C12") (pin "2") (pinfunction "2_2") (pintype "passive"))
      (node (ref "HX3") (pin "8") (pinfunction "IN_A+_8") (pintype "bidirectional"))
      (node (ref "R9") (pin "1") (pinfunction "1_1") (pintype "passive"))
    )
    (net (code "62") (name "Net-(HX3-VBG)") (class "Default")
      (node (ref "C10") (pin "2") (pinfunction "2_2") (pintype "passive"))
      (node (ref "HX3") (pin "6") (pinfunction "VBG_6") (pintype "bidirectional"))
    )
    (net (code "63") (name "Net-(HX3-VFB)") (class "Default")
      (node (ref "HX3") (pin "4") (pinfunction "VFB_4") (pintype "bidirectional"))
      (node (ref "R7") (pin "1") (pinfunction "1_1") (pintype "passive"))
      (node (ref "R8") (pin "2") (pinfunction "2_2") (pintype "passive"))
    )
    (net (code "64") (name "Net-(HX3-X1)") (class "Default")
      (node (ref "C39") (pin "1") (pinfunction "1_1") (pintype "passive"))
      (node (ref "HX3") (pin "14") (pinfunction "X1_14") (pintype "bidirectional"))
    )
    (net (code "65") (name "Net-(HX4-IN_A+)") (class "Default")
      (node (ref "C16") (pin "2") (pinfunction "2_2") (pintype "passive"))
      (node (ref "HX4") (pin "8") (pinfunction "IN_A+_8") (pintype "bidirectional"))
      (node (ref "R12") (pin "1") (pinfunction "1_1") (pintype "passive"))
    )
    (net (code "66") (name "Net-(HX4-VBG)") (class "Default")
      (node (ref "C14") (pin "2") (pinfunction "2_2") (pintype "passive"))
      (node (ref "HX4") (pin "6") (pinfunction "VBG_6") (pintype "bidirectional"))
    )
    (net (code "67") (name "Net-(HX4-VFB)") (class "Default")
      (node (ref "HX4") (pin "4") (pinfunction "VFB_4") (pintype "bidirectional"))
      (node (ref "R10") (pin "1") (pinfunction "1_1") (pintype "passive"))
      (node (ref "R11") (pin "2") (pinfunction "2_2") (pintype "passive"))
    )
    (net (code "68") (name "Net-(HX4-X1)") (class "Default")
      (node (ref "C38") (pin "1") (pinfunction "1_1") (pintype "passive"))
      (node (ref "HX4") (pin "14") (pinfunction "X1_14") (pintype "bidirectional"))
    )
    (net (code "69") (name "Net-(HX5-IN_A+)") (class "Default")
      (node (ref "C20") (pin "2") (pinfunction "2_2") (pintype "passive"))
      (node (ref "HX5") (pin "8") (pinfunction "IN_A+_8") (pintype "bidirectional"))
      (node (ref "R27") (pin "1") (pinfunction "1_1") (pintype "passive"))
    )
    (net (code "70") (name "Net-(HX5-VBG)") (class "Default")
      (node (ref "C18") (pin "2") (pinfunction "2_2") (pintype "passive"))
      (node (ref "HX5") (pin "6") (pinfunction "VBG_6") (pintype "bidirectional"))
    )
    (net (code "71") (name "Net-(HX5-VFB)") (class "Default")
      (node (ref "HX5") (pin "4") (pinfunction "VFB_4") (pintype "bidirectional"))
      (node (ref "R37") (pin "1") (pinfunction "1_1") (pintype "passive"))
      (node (ref "R38") (pin "2") (pinfunction "2_2") (pintype "passive"))
    )
    (net (code "72") (name "Net-(HX5-X1)") (class "Default")
      (node (ref "C34") (pin "1") (pinfunction "1_1") (pintype "passive"))
      (node (ref "HX5") (pin "14") (pinfunction "X1_14") (pintype "bidirectional"))
    )
    (net (code "73") (name "Net-(HX6-IN_A+)") (class "Default")
      (node (ref "C24") (pin "2") (pinfunction "2_2") (pintype "passive"))
      (node (ref "HX6") (pin "8") (pinfunction "IN_A+_8") (pintype "bidirectional"))
      (node (ref "R30") (pin "1") (pinfunction "1_1") (pintype "passive"))
    )
    (net (code "74") (name "Net-(HX6-VBG)") (class "Default")
      (node (ref "C22") (pin "2") (pinfunction "2_2") (pintype "passive"))
      (node (ref "HX6") (pin "6") (pinfunction "VBG_6") (pintype "bidirectional"))
    )
    (net (code "75") (name "Net-(HX6-VFB)") (class "Default")
      (node (ref "HX6") (pin "4") (pinfunction "VFB_4") (pintype "bidirectional"))
      (node (ref "R28") (pin "1") (pinfunction "1_1") (pintype "passive"))
      (node (ref "R29") (pin "2") (pinfunction "2_2") (pintype "passive"))
    )
    (net (code "76") (name "Net-(HX6-X1)") (class "Default")
      (node (ref "C35") (pin "1") (pinfunction "1_1") (pintype "passive"))
      (node (ref "HX6") (pin "14") (pinfunction "X1_14") (pintype "bidirectional"))
    )
    (net (code "77") (name "Net-(HX7-IN_A+)") (class "Default")
      (node (ref "C28") (pin "2") (pinfunction "2_2") (pintype "passive"))
      (node (ref "HX7") (pin "8") (pinfunction "IN_A+_8") (pintype "bidirectional"))
      (node (ref "R33") (pin "1") (pinfunction "1_1") (pintype "passive"))
    )
    (net (code "78") (name "Net-(HX7-VBG)") (class "Default")
      (node (ref "C26") (pin "2") (pinfunction "2_2") (pintype "passive"))
      (node (ref "HX7") (pin "6") (pinfunction "VBG_6") (pintype "bidirectional"))
    )
    (net (code "79") (name "Net-(HX7-VFB)") (class "Default")
      (node (ref "HX7") (pin "4") (pinfunction "VFB_4") (pintype "bidirectional"))
      (node (ref "R31") (pin "1") (pinfunction "1_1") (pintype "passive"))
      (node (ref "R32") (pin "2") (pinfunction "2_2") (pintype "passive"))
    )
    (net (code "80") (name "Net-(HX7-X1)") (class "Default")
      (node (ref "C36") (pin "1") (pinfunction "1_1") (pintype "passive"))
      (node (ref "HX7") (pin "14") (pinfunction "X1_14") (pintype "bidirectional"))
    )
    (net (code "81") (name "Net-(HX8-IN_A+)") (class "Default")
      (node (ref "C32") (pin "2") (pinfunction "2_2") (pintype "passive"))
      (node (ref "HX8") (pin "8") (pinfunction "IN_A+_8") (pintype "bidirectional"))
      (node (ref "R36") (pin "1") (pinfunction "1_1") (pintype "passive"))
    )
    (net (code "82") (name "Net-(HX8-VBG)") (class "Default")
      (node (ref "C30") (pin "2") (pinfunction "2_2") (pintype "passive"))
      (node (ref "HX8") (pin "6") (pinfunction "VBG_6") (pintype "bidirectional"))
    )
    (net (code "83") (name "Net-(HX8-VFB)") (class "Default")
      (node (ref "HX8") (pin "4") (pinfunction "VFB_4") (pintype "bidirectional"))
      (node (ref "R34") (pin "1") (pinfunction "1_1") (pintype "passive"))
      (node (ref "R35") (pin "2") (pinfunction "2_2") (pintype "passive"))
    )
    (net (code "84") (name "Net-(HX8-X1)") (class "Default")
      (node (ref "C37") (pin "1") (pinfunction "1_1") (pintype "passive"))
      (node (ref "HX8") (pin "14") (pinfunction "X1_14") (pintype "bidirectional"))
    )
    (net (code "85") (name "Net-(U$7-4)") (class "Default")
      (node (ref "R6") (pin "2") (pinfunction "2_2") (pintype "passive"))
      (node (ref "U$7") (pin "P$4") (pinfunction "4_P$4") (pintype "passive"))
    )
    (net (code "86") (name "Net-(U$10-4)") (class "Default")
      (node (ref "R9") (pin "2") (pinfunction "2_2") (pintype "passive"))
      (node (ref "U$10") (pin "P$4") (pinfunction "4_P$4") (pintype "passive"))
    )
    (net (code "87") (name "Net-(U$13-4)") (class "Default")
      (node (ref "R12") (pin "2") (pinfunction "2_2") (pintype "passive"))
      (node (ref "U$13") (pin "P$4") (pinfunction "4_P$4") (pintype "passive"))
    )
    (net (code "88") (name "Net-(U$18-4)") (class "Default")
      (node (ref "R30") (pin "2") (pinfunction "2_2") (pintype "passive"))
      (node (ref "U$18") (pin "P$4") (pinfunction "4_P$4") (pintype "passive"))
    )
    (net (code "89") (name "Net-(U$20-4)") (class "Default")
      (node (ref "R33") (pin "2") (pinfunction "2_2") (pintype "passive"))
      (node (ref "U$20") (pin "P$4") (pinfunction "4_P$4") (pintype "passive"))
    )
    (net (code "90") (name "Net-(U$22-4)") (class "Default")
      (node (ref "R36") (pin "2") (pinfunction "2_2") (pintype "passive"))
      (node (ref "U$22") (pin "P$4") (pinfunction "4_P$4") (pintype "passive"))
    )
    (net (code "91") (name "VCC") (class "Default")
      (node (ref "C1") (pin "1") (pinfunction "1_1") (pintype "passive"))
      (node (ref "C13") (pin "1") (pinfunction "1_1") (pintype "passive"))
      (node (ref "C17") (pin "1") (pinfunction "1_1") (pintype "passive"))
      (node (ref "C21") (pin "1") (pinfunction "1_1") (pintype "passive"))
      (node (ref "C25") (pin "1") (pinfunction "1_1") (pintype "passive"))
      (node (ref "C29") (pin "1") (pinfunction "1_1") (pintype "passive"))
      (node (ref "C5") (pin "1") (pinfunction "1_1") (pintype "passive"))
      (node (ref "C9") (pin "1") (pinfunction "1_1") (pintype "passive"))
      (node (ref "HX1") (pin "1") (pinfunction "VSUP_1") (pintype "bidirectional"))
      (node (ref "HX1") (pin "15") (pinfunction "RATE_15") (pintype "bidirectional"))
      (node (ref "HX1") (pin "16") (pinfunction "DVDD_16") (pintype "bidirectional"))
      (node (ref "HX2") (pin "1") (pinfunction "VSUP_1") (pintype "bidirectional"))
      (node (ref "HX2") (pin "15") (pinfunction "RATE_15") (pintype "bidirectional"))
      (node (ref "HX2") (pin "16") (pinfunction "DVDD_16") (pintype "bidirectional"))
      (node (ref "HX3") (pin "1") (pinfunction "VSUP_1") (pintype "bidirectional"))
      (node (ref "HX3") (pin "15") (pinfunction "RATE_15") (pintype "bidirectional"))
      (node (ref "HX3") (pin "16") (pinfunction "DVDD_16") (pintype "bidirectional"))
      (node (ref "HX4") (pin "1") (pinfunction "VSUP_1") (pintype "bidirectional"))
      (node (ref "HX4") (pin "15") (pinfunction "RATE_15") (pintype "bidirectional"))
      (node (ref "HX4") (pin "16") (pinfunction "DVDD_16") (pintype "bidirectional"))
      (node (ref "HX5") (pin "1") (pinfunction "VSUP_1") (pintype "bidirectional"))
      (node (ref "HX5") (pin "15") (pinfunction "RATE_15") (pintype "bidirectional"))
      (node (ref "HX5") (pin "16") (pinfunction "DVDD_16") (pintype "bidirectional"))
      (node (ref "HX6") (pin "1") (pinfunction "VSUP_1") (pintype "bidirectional"))
      (node (ref "HX6") (pin "15") (pinfunction "RATE_15") (pintype "bidirectional"))
      (node (ref "HX6") (pin "16") (pinfunction "DVDD_16") (pintype "bidirectional"))
      (node (ref "HX7") (pin "1") (pinfunction "VSUP_1") (pintype "bidirectional"))
      (node (ref "HX7") (pin "15") (pinfunction "RATE_15") (pintype "bidirectional"))
      (node (ref "HX7") (pin "16") (pinfunction "DVDD_16") (pintype "bidirectional"))
      (node (ref "HX8") (pin "1") (pinfunction "VSUP_1") (pintype "bidirectional"))
      (node (ref "HX8") (pin "15") (pinfunction "RATE_15") (pintype "bidirectional"))
      (node (ref "HX8") (pin "16") (pinfunction "DVDD_16") (pintype "bidirectional"))
      (node (ref "MAPLE_MINI") (pin "VIN") (pinfunction "VIN_VIN") (pintype "bidirectional"))
      (node (ref "MAX485") (pin "8") (pinfunction "+5V_8") (pintype "power_in"))
      (node (ref "R13") (pin "2") (pinfunction "2_2") (pintype "passive"))
      (node (ref "R2") (pin "2") (pinfunction "2_2") (pintype "passive"))
      (node (ref "U$1") (pin "2") (pinfunction "E_2") (pintype "passive"))
      (node (ref "U$11") (pin "2") (pinfunction "E_2") (pintype "passive"))
      (node (ref "U$12") (pin "2") (pinfunction "E_2") (pintype "passive"))
      (node (ref "U$17") (pin "2") (pinfunction "E_2") (pintype "passive"))
      (node (ref "U$19") (pin "2") (pinfunction "E_2") (pintype "passive"))
      (node (ref "U$2") (pin "+") (pinfunction "+_+") (pintype "passive"))
      (node (ref "U$21") (pin "2") (pinfunction "E_2") (pintype "passive"))
      (node (ref "U$23") (pin "3") (pinfunction "3_3") (pintype "passive"))
      (node (ref "U$4") (pin "+") (pinfunction "+_+") (pintype "passive"))
      (node (ref "U$6") (pin "2") (pinfunction "E_2") (pintype "passive"))
      (node (ref "U$9") (pin "2") (pinfunction "E_2") (pintype "passive"))
    )
    (net (code "92") (name "unconnected-(HX1-X0-Pad13)") (class "Default")
      (node (ref "HX1") (pin "13") (pinfunction "X0_13") (pintype "bidirectional"))
    )
    (net (code "93") (name "unconnected-(HX2-X0-Pad13)") (class "Default")
      (node (ref "HX2") (pin "13") (pinfunction "X0_13") (pintype "bidirectional"))
    )
    (net (code "94") (name "unconnected-(HX3-X0-Pad13)") (class "Default")
      (node (ref "HX3") (pin "13") (pinfunction "X0_13") (pintype "bidirectional"))
    )
    (net (code "95") (name "unconnected-(HX4-X0-Pad13)") (class "Default")
      (node (ref "HX4") (pin "13") (pinfunction "X0_13") (pintype "bidirectional"))
    )
    (net (code "96") (name "unconnected-(HX5-X0-Pad13)") (class "Default")
      (node (ref "HX5") (pin "13") (pinfunction "X0_13") (pintype "bidirectional"))
    )
    (net (code "97") (name "unconnected-(HX6-X0-Pad13)") (class "Default")
      (node (ref "HX6") (pin "13") (pinfunction "X0_13") (pintype "bidirectional"))
    )
    (net (code "98") (name "unconnected-(HX7-X0-Pad13)") (class "Default")
      (node (ref "HX7") (pin "13") (pinfunction "X0_13") (pintype "bidirectional"))
    )
    (net (code "99") (name "unconnected-(HX8-X0-Pad13)") (class "Default")
      (node (ref "HX8") (pin "13") (pinfunction "X0_13") (pintype "bidirectional"))
    )
    (net (code "100") (name "unconnected-(MAPLE_MINI-4-PadX4)") (class "Default")
      (node (ref "MAPLE_MINI") (pin "X4") (pinfunction "4_X4") (pintype "bidirectional"))
    )
    (net (code "101") (name "unconnected-(MAPLE_MINI-5-PadX5)") (class "Default")
      (node (ref "MAPLE_MINI") (pin "X5") (pinfunction "5_X5") (pintype "bidirectional"))
    )
    (net (code "102") (name "unconnected-(MAPLE_MINI-7-PadX7)") (class "Default")
      (node (ref "MAPLE_MINI") (pin "X7") (pinfunction "7_X7") (pintype "bidirectional"))
    )
    (net (code "103") (name "unconnected-(MAPLE_MINI-9-PadX9)") (class "Default")
      (node (ref "MAPLE_MINI") (pin "X9") (pinfunction "9_X9") (pintype "bidirectional"))
    )
    (net (code "104") (name "unconnected-(MAPLE_MINI-10-PadX10)") (class "Default")
      (node (ref "MAPLE_MINI") (pin "X10") (pinfunction "10_X10") (pintype "bidirectional"))
    )
    (net (code "105") (name "unconnected-(MAPLE_MINI-11-PadX11)") (class "Default")
      (node (ref "MAPLE_MINI") (pin "X11") (pinfunction "11_X11") (pintype "bidirectional"))
    )
    (net (code "106") (name "unconnected-(MAPLE_MINI-12-PadX12)") (class "Default")
      (node (ref "MAPLE_MINI") (pin "X12") (pinfunction "12_X12") (pintype "bidirectional"))
    )
    (net (code "107") (name "unconnected-(MAPLE_MINI-13-PadX13)") (class "Default")
      (node (ref "MAPLE_MINI") (pin "X13") (pinfunction "13_X13") (pintype "bidirectional"))
    )
    (net (code "108") (name "unconnected-(MAPLE_MINI-14-PadX14)") (class "Default")
      (node (ref "MAPLE_MINI") (pin "X14") (pinfunction "14_X14") (pintype "bidirectional"))
    )
    (net (code "109") (name "unconnected-(MAPLE_MINI-17-PadX17)") (class "Default")
      (node (ref "MAPLE_MINI") (pin "X17") (pinfunction "17_X17") (pintype "bidirectional"))
    )
    (net (code "110") (name "unconnected-(MAPLE_MINI-23-PadX23)") (class "Default")
      (node (ref "MAPLE_MINI") (pin "X23") (pinfunction "23_X23") (pintype "bidirectional"))
    )
    (net (code "111") (name "unconnected-(MAPLE_MINI-24-PadX24)") (class "Default")
      (node (ref "MAPLE_MINI") (pin "X24") (pinfunction "24_X24") (pintype "bidirectional"))
    )
    (net (code "112") (name "unconnected-(MAPLE_MINI-PadAV+)") (class "Default")
      (node (ref "MAPLE_MINI") (pin "AV+") (pinfunction "AV+_AV+") (pintype "bidirectional"))
    )
    (net (code "113") (name "unconnected-(MAPLE_MINI-PadAV-)") (class "Default")
      (node (ref "MAPLE_MINI") (pin "AV-") (pinfunction "AV-_AV-") (pintype "bidirectional"))
    )
    (net (code "114") (name "unconnected-(MAPLE_MINI-PadBUT)") (class "Default")
      (node (ref "MAPLE_MINI") (pin "BUT") (pinfunction "BUT_BUT") (pintype "bidirectional"))
    )
    (net (code "115") (name "unconnected-(MAPLE_MINI-PadRESET)") (class "Default")
      (node (ref "MAPLE_MINI") (pin "RESET") (pinfunction "RESET_RESET") (pintype "bidirectional"))
    )
    (net (code "116") (name "unconnected-(MAPLE_MINI-PadVBAT)") (class "Default")
      (node (ref "MAPLE_MINI") (pin "VBAT") (pinfunction "VBAT_VBAT") (pintype "bidirectional"))
    )
    (net (code "117") (name "unconnected-(MAPLE_MINI-PadVCC)") (class "Default")
      (node (ref "MAPLE_MINI") (pin "VCC") (pinfunction "VCC_VCC") (pintype "bidirectional"))
    )
  )
)
